# USB.net
KiCad netlist of a schematic drawn in Altium Designer
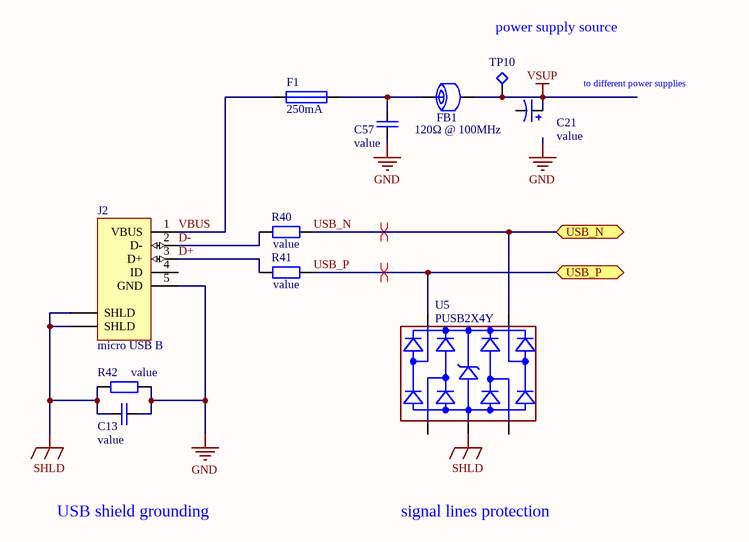
[diagram p0: USB.SchDoc]

(export (version "E")
  (design (tool "Eeschema 10.0.6"))
  (components
    (comp (ref "C13")
      (value "value")
      (footprint "C_0603")
      (description "Generic capacitor")
      (fields (field (name "Comment") "comment"))
      (libsource (lib "DAQ") (part "Capacitor"))
    )
    (comp (ref "C21")
      (value "value")
      (footprint "Tantalum Case A")
      (description "Generic polarized capacitor")
      (fields (field (name "Comment") "comment"))
      (libsource (lib "DAQ") (part "Capacitor - polarized"))
    )
    (comp (ref "C57")
      (value "value")
      (footprint "C_0603")
      (description "Generic capacitor")
      (fields (field (name "Comment") "comment"))
      (libsource (lib "DAQ") (part "Capacitor"))
    )
    (comp (ref "F1")
      (value "250mA")
      (footprint "PPTCF 1206")
      (description "Resettable Fuse, PPTC, 1206 (3216 Metric), POLYFUSE 1206L Series, 16 VDC, 250 mA, 500 mA, 0.08 s")
      (fields (field (name "MANUFACTURER") "Littelfuse"))
      (libsource (lib "DAQ") (part "1206L025YR"))
    )
    (comp (ref "FB1")
      (value "120Ω @ 100MHz")
      (footprint "SMD_0805")
      (description "Ferrite Bead, 0805 [2012 Metric], 120 ohm, 800 mA, BLM21A Series, 0.15 ohm, ± 25%")
      (fields (field (name "MANUFACTURER") "Murata"))
      (libsource (lib "DAQ") (part "BLM21AG121SN1D"))
    )
    (comp (ref "J2")
      (value "micro USB B")
      (footprint "MICRO_USB_A")
      (description "USB Connector, Micro USB Type AB, USB 2.0, Receptacle, 5 Ways, Surface Mount, Right Angle")
      (fields (field (name "MANUFACTURER") "FCI"))
      (libsource (lib "DAQ") (part "10104111-0001LF"))
    )
    (comp (ref "R40")
      (value "value")
      (footprint "R_0603")
      (description "Generic resistor")
      (fields (field (name "Comment") "comment"))
      (libsource (lib "DAQ") (part "Resistor"))
    )
    (comp (ref "R41")
      (value "value")
      (footprint "R_0603")
      (description "Generic resistor")
      (fields (field (name "Comment") "comment"))
      (libsource (lib "DAQ") (part "Resistor"))
    )
    (comp (ref "R42")
      (value "value")
      (footprint "R_0603")
      (description "Generic resistor")
      (fields (field (name "Comment") "comment"))
      (libsource (lib "DAQ") (part "Resistor"))
    )
    (comp (ref "TP10")
      (value "test point 1.5mm")
      (footprint "TP1_FULL")
      (description "Test point ,1.5mm diameter, no hole")
      (libsource (lib "DAQ") (part "Test Point"))
    )
    (comp (ref "U5")
      (value "PUSB2X4Y")
      (footprint "SOT363")
      (description "ESD Protection Device, 3.8 V, SC-88, 6 Pins, PUSB2 Series")
      (fields (field (name "MANUFACTURER") "Multicomp"))
      (libsource (lib "DAQ") (part "PUSB2X4Y"))
    )
  )
  (nets
    (net (code "1") (name "/D+") (class "Default")
      (node (ref "J2") (pin "3") (pinfunction "D+_3") (pintype "bidirectional"))
      (node (ref "R41") (pin "1") (pintype "passive"))
    )
    (net (code "2") (name "/D-") (class "Default")
      (node (ref "J2") (pin "2") (pinfunction "D-_2") (pintype "bidirectional"))
      (node (ref "R40") (pin "1") (pintype "passive"))
    )
    (net (code "3") (name "/USB_N") (class "Default")
      (node (ref "R40") (pin "2") (pintype "passive"))
      (node (ref "U5") (pin "4") (pinfunction "4_4") (pintype "passive"))
    )
    (net (code "4") (name "/USB_P") (class "Default")
      (node (ref "R41") (pin "2") (pintype "passive"))
      (node (ref "U5") (pin "6") (pinfunction "6_6") (pintype "passive"))
    )
    (net (code "5") (name "/VBUS") (class "Default")
      (node (ref "F1") (pin "1") (pinfunction "1_1") (pintype "passive"))
      (node (ref "J2") (pin "1") (pinfunction "VBUS_1") (pintype "power_in"))
    )
    (net (code "6") (name "GND") (class "Default")
      (node (ref "C13") (pin "1") (pinfunction "1_1") (pintype "passive"))
      (node (ref "C57") (pin "2") (pinfunction "2_2") (pintype "passive"))
      (node (ref "J2") (pin "5") (pinfunction "GND_5") (pintype "power_in"))
      (node (ref "R42") (pin "1") (pintype "passive"))
    )
    (net (code "7") (name "Net-(C57-Pad1)") (class "Default")
      (node (ref "C57") (pin "1") (pinfunction "1_1") (pintype "passive"))
      (node (ref "F1") (pin "2") (pinfunction "2_2") (pintype "passive"))
      (node (ref "FB1") (pin "1") (pintype "passive"))
    )
    (net (code "8") (name "SHLD") (class "Default")
      (node (ref "C13") (pin "2") (pinfunction "2_2") (pintype "passive"))
      (node (ref "J2") (pin "6") (pinfunction "SHLD_6") (pintype "passive"))
      (node (ref "J2") (pin "7") (pinfunction "SHLD_7") (pintype "passive"))
      (node (ref "R42") (pin "2") (pintype "passive"))
      (node (ref "U5") (pin "2") (pinfunction "2_2") (pintype "passive"))
    )
    (net (code "9") (name "VSUP") (class "Default")
      (node (ref "C21") (pin "1") (pinfunction "1_1") (pintype "passive"))
      (node (ref "FB1") (pin "2") (pintype "passive"))
      (node (ref "TP10") (pin "1") (pinfunction "1_1") (pintype "passive"))
    )
    (net (code "10") (name "unconnected-(C21-Pad2)") (class "Default")
      (node (ref "C21") (pin "2") (pinfunction "2_2") (pintype "passive"))
    )
    (net (code "11") (name "unconnected-(J2-ID-Pad4)") (class "Default")
      (node (ref "J2") (pin "4") (pinfunction "ID_4") (pintype "passive"))
    )
    (net (code "12") (name "unconnected-(U5-Pad1)") (class "Default")
      (node (ref "U5") (pin "1") (pinfunction "1_1") (pintype "passive"))
    )
    (net (code "13") (name "unconnected-(U5-Pad3)") (class "Default")
      (node (ref "U5") (pin "3") (pinfunction "3_3") (pintype "passive"))
    )
  )
)
